# GeneratedSystem-01.net
KiCad netlist of a schematic drawn in Altium Designer
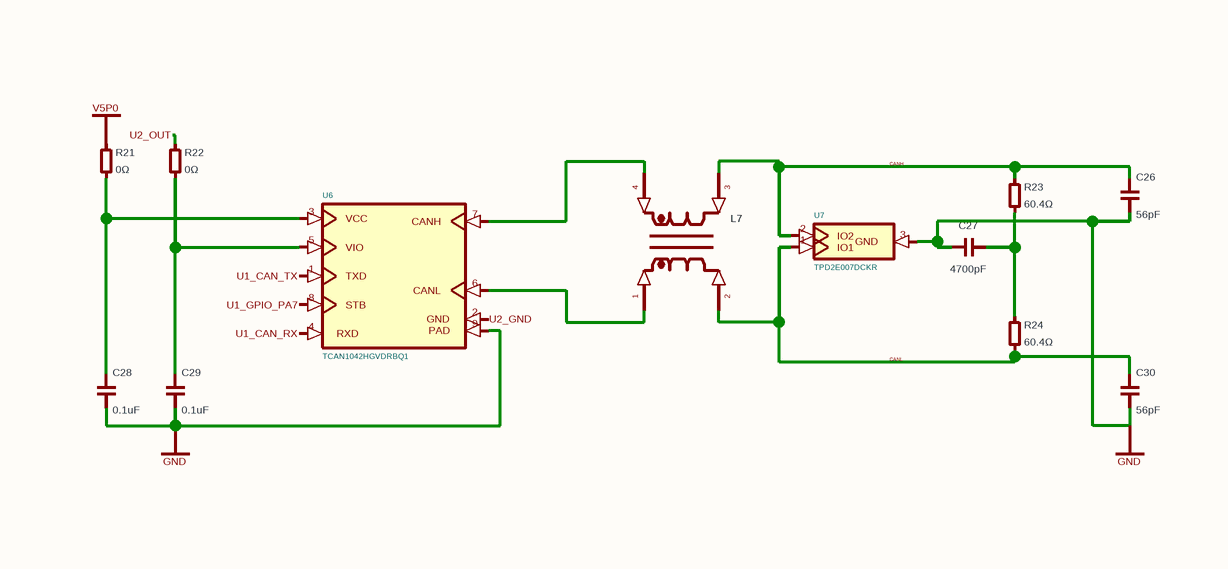
[diagram p0: GeneratedSystem-01.SchDoc]

(export (version "E")
  (design (tool "Eeschema 10.0.6"))
  (components
    (comp (ref "C26") (value "56pF") (libsource (lib "altium-import") (part "root_0_capacitor_down_")))
    (comp (ref "C27") (value "4700pF") (libsource (lib "altium-import") (part "root_0_capacitor_right_")))
    (comp (ref "C28") (value "0.1uF") (libsource (lib "altium-import") (part "root_0_capacitor_down_")))
    (comp (ref "C29") (value "0.1uF") (libsource (lib "altium-import") (part "root_0_capacitor_down_")))
    (comp (ref "C30") (value "56pF") (libsource (lib "altium-import") (part "root_0_capacitor_down_")))
    (comp (ref "L7") (value "~") (libsource (lib "altium-import") (part "root_0_L7_")))
    (comp (ref "R21") (value "0Ω") (libsource (lib "altium-import") (part "root_0_boxresistor_down_")))
    (comp (ref "R22") (value "0Ω") (libsource (lib "altium-import") (part "root_0_boxresistor_down_")))
    (comp (ref "R23") (value "60.4Ω") (libsource (lib "altium-import") (part "root_0_boxresistor_down_")))
    (comp (ref "R24") (value "60.4Ω") (libsource (lib "altium-import") (part "root_0_boxresistor_down_")))
    (comp (ref "U6") (value "~") (libsource (lib "altium-import") (part "root_0_U6_")))
    (comp (ref "U7") (value "~") (libsource (lib "altium-import") (part "root_0_U7_")))
  )
  (nets
    (net (code "1") (name "/U1_CAN_RX") (class "Default")
      (node (ref "U6") (pin "4") (pinfunction "RXD_4") (pintype "input"))
    )
    (net (code "2") (name "/U1_CAN_TX") (class "Default")
      (node (ref "U6") (pin "1") (pinfunction "TXD_1") (pintype "input"))
    )
    (net (code "3") (name "/U1_GPIO_PA7") (class "Default")
      (node (ref "U6") (pin "8") (pinfunction "STB_8") (pintype "input"))
    )
    (net (code "4") (name "/U2_GND") (class "Default")
      (node (ref "U6") (pin "2") (pinfunction "GND_2") (pintype "input"))
    )
    (net (code "5") (name "/U2_OUT") (class "Default")
      (node (ref "R22") (pin "1") (pinfunction "anode_1") (pintype "input"))
    )
    (net (code "6") (name "GND") (class "Default")
      (node (ref "C26") (pin "2") (pinfunction "cathode_2") (pintype "input"))
      (node (ref "C27") (pin "1") (pinfunction "pos_1") (pintype "input"))
      (node (ref "C28") (pin "2") (pinfunction "cathode_2") (pintype "input"))
      (node (ref "C29") (pin "2") (pinfunction "cathode_2") (pintype "input"))
      (node (ref "C30") (pin "2") (pinfunction "cathode_2") (pintype "input"))
      (node (ref "U6") (pin "9") (pinfunction "PAD_9") (pintype "input"))
      (node (ref "U7") (pin "3") (pinfunction "GND_3") (pintype "input"))
    )
    (net (code "7") (name "Net-(C26-anode)") (class "Default")
      (node (ref "C26") (pin "1") (pinfunction "anode_1") (pintype "input"))
      (node (ref "L7") (pin "3") (pinfunction "pin3_3") (pintype "input"))
      (node (ref "R23") (pin "1") (pinfunction "anode_1") (pintype "input"))
      (node (ref "U7") (pin "2") (pinfunction "IO2_2") (pintype "input"))
    )
    (net (code "8") (name "Net-(C27-neg)") (class "Default")
      (node (ref "C27") (pin "2") (pinfunction "neg_2") (pintype "input"))
      (node (ref "R23") (pin "2") (pinfunction "cathode_2") (pintype "input"))
      (node (ref "R24") (pin "1") (pinfunction "anode_1") (pintype "input"))
    )
    (net (code "9") (name "Net-(C28-anode)") (class "Default")
      (node (ref "C28") (pin "1") (pinfunction "anode_1") (pintype "input"))
      (node (ref "R21") (pin "2") (pinfunction "cathode_2") (pintype "input"))
      (node (ref "U6") (pin "3") (pinfunction "VCC_3") (pintype "input"))
    )
    (net (code "10") (name "Net-(C29-anode)") (class "Default")
      (node (ref "C29") (pin "1") (pinfunction "anode_1") (pintype "input"))
      (node (ref "R22") (pin "2") (pinfunction "cathode_2") (pintype "input"))
      (node (ref "U6") (pin "5") (pinfunction "VIO_5") (pintype "input"))
    )
    (net (code "11") (name "Net-(C30-anode)") (class "Default")
      (node (ref "C30") (pin "1") (pinfunction "anode_1") (pintype "input"))
      (node (ref "L7") (pin "2") (pinfunction "pin2_2") (pintype "input"))
      (node (ref "R24") (pin "2") (pinfunction "cathode_2") (pintype "input"))
      (node (ref "U7") (pin "1") (pinfunction "IO1_1") (pintype "input"))
    )
    (net (code "12") (name "Net-(L7-pin1)") (class "Default")
      (node (ref "L7") (pin "1") (pinfunction "pin1_1") (pintype "input"))
      (node (ref "U6") (pin "6") (pinfunction "CANL_6") (pintype "input"))
    )
    (net (code "13") (name "Net-(L7-pin4)") (class "Default")
      (node (ref "L7") (pin "4") (pinfunction "pin4_4") (pintype "input"))
      (node (ref "U6") (pin "7") (pinfunction "CANH_7") (pintype "input"))
    )
    (net (code "14") (name "V5P0") (class "Default")
      (node (ref "R21") (pin "1") (pinfunction "anode_1") (pintype "input"))
    )
  )
)
